# POWER_SUPPLY.net
KiCad netlist of a schematic drawn in Altium Designer
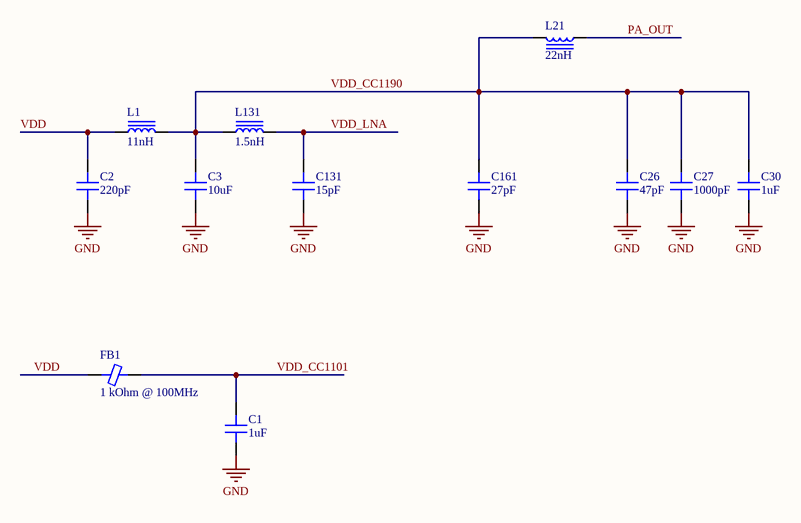
[diagram p0: POWER_SUPPLY.SchDoc]

(export (version "E")
  (design (tool "Eeschema 10.0.6"))
  (components
    (comp (ref "C1")
      (value "1uF")
      (footprint "CAP 0402/1005")
      (description "CAP CER 1UF 6.3V X5R 0402")
      (fields
        (field (name "PART NUMBER") "GRM155R60J105KE19D")
        (field (name "MANUFACTURER") "Murata Electronics North America")
      )
      (libsource (lib "Celestial Library Database") (part "Capacitor"))
    )
    (comp (ref "C2")
      (value "220pF")
      (footprint "CAP 0402/1005")
      (description "CAP CER 220PF 50V NP0 0402")
      (fields
        (field (name "PART NUMBER") "GCM1555C1H221JA16D")
        (field (name "MANUFACTURER") "Murata Electronics North America")
      )
      (libsource (lib "Celestial Library Database") (part "Capacitor"))
    )
    (comp (ref "C3")
      (value "10uF")
      (footprint "CAP 0402/1005")
      (description "CAP CER 10UF 6.3V X5R 0402")
      (fields
        (field (name "PART NUMBER") "C1005X5R0J106M050BC")
        (field (name "MANUFACTURER") "TDK Corporation")
      )
      (libsource (lib "Celestial Library Database") (part "Capacitor"))
    )
    (comp (ref "C26")
      (value "47pF")
      (footprint "CAP 0402/1005")
      (description "CAP CER 47PF 50V NP0 0402")
      (fields
        (field (name "PART NUMBER") "GRM1555C1H470JA01D")
        (field (name "MANUFACTURER") "Murata Electronics North America")
      )
      (libsource (lib "Celestial Library Database") (part "Capacitor"))
    )
    (comp (ref "C27")
      (value "1000pF")
      (footprint "CAP 0402/1005")
      (description "CAP CER 1000PF 50V NP0 0402")
      (fields
        (field (name "PART NUMBER") "GRM1555C1H102JA01D")
        (field (name "MANUFACTURER") "Murata Electronics North America")
      )
      (libsource (lib "Celestial Library Database") (part "Capacitor"))
    )
    (comp (ref "C30")
      (value "1uF")
      (footprint "CAP 0402/1005")
      (description "CAP CER 1UF 6.3V X5R 0402")
      (fields
        (field (name "PART NUMBER") "GRM155R60J105KE19D")
        (field (name "MANUFACTURER") "Murata Electronics North America")
      )
      (libsource (lib "Celestial Library Database") (part "Capacitor"))
    )
    (comp (ref "C131")
      (value "15pF")
      (footprint "CAP 0402/1005")
      (description "CAP CER 15PF 50V NP0 0402")
      (fields
        (field (name "PART NUMBER") "GRM1555C1H150JA01D")
        (field (name "MANUFACTURER") "Murata Electronics North America")
      )
      (libsource (lib "Celestial Library Database") (part "Capacitor"))
    )
    (comp (ref "C161")
      (value "27pF")
      (footprint "CAP 0402/1005")
      (description "CAP CER 27PF 50V NP0 0402")
      (fields
        (field (name "PART NUMBER") "GRM1555C1H270JA01D")
        (field (name "MANUFACTURER") "Murata Electronics North America")
      )
      (libsource (lib "Celestial Library Database") (part "Capacitor"))
    )
    (comp (ref "FB1")
      (value "1 kOhm @ 100MHz")
      (footprint "FER 0402/1005")
      (description "FERRITE CHIP 1000 OHM 250MA 0402")
      (fields
        (field (name "PART NUMBER") "BLM15HD102SN1D")
        (field (name "MANUFACTURER") "Murata Electronics North America")
      )
      (libsource (lib "Celestial Library Database") (part "Ferrite Chip"))
    )
    (comp (ref "L1")
      (value "11nH")
      (footprint "IND 0402/1005 RF WW")
      (description "FIXED IND 11NH 500MA 140 MOHM")
      (fields
        (field (name "PART NUMBER") "LQW15AN11NJ00D")
        (field (name "MANUFACTURER") "Murata Electronics North America")
      )
      (libsource (lib "Celestial Library Database") (part "Inductor"))
    )
    (comp (ref "L21")
      (value "22nH")
      (footprint "IND 0402/1005 RF WW")
      (description "FIXED IND 22NH 310MA 300 MOHM")
      (fields
        (field (name "PART NUMBER") "LQW15AN22NH00D")
        (field (name "MANUFACTURER") "Murata Electronics North America")
      )
      (libsource (lib "Celestial Library Database") (part "Inductor"))
    )
    (comp (ref "L131")
      (value "1.5nH")
      (footprint "IND 0402/1005 RF WW")
      (description "FIXED IND 1.5NH 1A 30 MOHM 0402")
      (fields
        (field (name "PART NUMBER") "LQW15AN1N5D00D")
        (field (name "MANUFACTURER") "Murata Electronics North America")
      )
      (libsource (lib "Celestial Library Database") (part "Inductor"))
    )
  )
  (nets
    (net (code "1") (name "/PA_OUT") (class "Default")
      (node (ref "L21") (pin "1") (pinfunction "1_1") (pintype "passive"))
    )
    (net (code "2") (name "/VDD") (class "Default")
      (node (ref "C2") (pin "2") (pinfunction "2_2") (pintype "passive"))
      (node (ref "FB1") (pin "1") (pinfunction "1_1") (pintype "passive"))
      (node (ref "L1") (pin "1") (pinfunction "1_1") (pintype "passive"))
    )
    (net (code "3") (name "/VDD_CC1101") (class "Default")
      (node (ref "C1") (pin "2") (pinfunction "2_2") (pintype "passive"))
      (node (ref "FB1") (pin "2") (pinfunction "2_2") (pintype "passive"))
    )
    (net (code "4") (name "/VDD_CC1190") (class "Default")
      (node (ref "C161") (pin "2") (pinfunction "2_2") (pintype "passive"))
      (node (ref "C26") (pin "2") (pinfunction "2_2") (pintype "passive"))
      (node (ref "C27") (pin "2") (pinfunction "2_2") (pintype "passive"))
      (node (ref "C3") (pin "2") (pinfunction "2_2") (pintype "passive"))
      (node (ref "C30") (pin "2") (pinfunction "2_2") (pintype "passive"))
      (node (ref "L1") (pin "2") (pinfunction "2_2") (pintype "passive"))
      (node (ref "L131") (pin "1") (pinfunction "1_1") (pintype "passive"))
      (node (ref "L21") (pin "2") (pinfunction "2_2") (pintype "passive"))
    )
    (net (code "5") (name "/VDD_LNA") (class "Default")
      (node (ref "C131") (pin "2") (pinfunction "2_2") (pintype "passive"))
      (node (ref "L131") (pin "2") (pinfunction "2_2") (pintype "passive"))
    )
    (net (code "6") (name "GND") (class "Default")
      (node (ref "C1") (pin "1") (pinfunction "1_1") (pintype "passive"))
      (node (ref "C131") (pin "1") (pinfunction "1_1") (pintype "passive"))
      (node (ref "C161") (pin "1") (pinfunction "1_1") (pintype "passive"))
      (node (ref "C2") (pin "1") (pinfunction "1_1") (pintype "passive"))
      (node (ref "C26") (pin "1") (pinfunction "1_1") (pintype "passive"))
      (node (ref "C27") (pin "1") (pinfunction "1_1") (pintype "passive"))
      (node (ref "C3") (pin "1") (pinfunction "1_1") (pintype "passive"))
      (node (ref "C30") (pin "1") (pinfunction "1_1") (pintype "passive"))
    )
  )
)
